# Retrotink5x_backwards.net
KiCad netlist of a schematic drawn in EAGLE
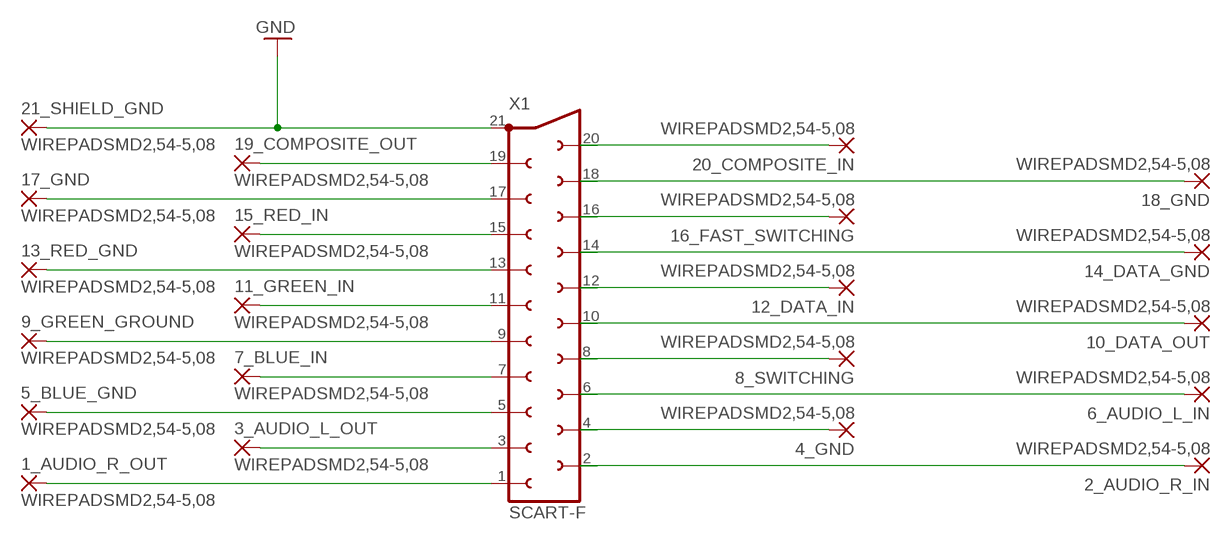
[diagram p0: schematic, sheet 1]

(export (version "E")
  (design (tool "Eeschema 10.0.6"))
  (components
    (comp (ref "1_AUDIO_R_OUT")
      (value "WIREPADSMD2,54-5,08")
      (footprint "eagle-import:SMD2,54-5,08")
      (libsource (lib "eagle-import") (part "WIREPADSMD2,54-5,08"))
    )
    (comp (ref "2_AUDIO_R_IN")
      (value "WIREPADSMD2,54-5,08")
      (footprint "eagle-import:SMD2,54-5,08")
      (libsource (lib "eagle-import") (part "WIREPADSMD2,54-5,08"))
    )
    (comp (ref "3_AUDIO_L_OUT")
      (value "WIREPADSMD2,54-5,08")
      (footprint "eagle-import:SMD2,54-5,08")
      (libsource (lib "eagle-import") (part "WIREPADSMD2,54-5,08"))
    )
    (comp (ref "4_GND")
      (value "WIREPADSMD2,54-5,08")
      (footprint "eagle-import:SMD2,54-5,08")
      (libsource (lib "eagle-import") (part "WIREPADSMD2,54-5,08"))
    )
    (comp (ref "5_BLUE_GND")
      (value "WIREPADSMD2,54-5,08")
      (footprint "eagle-import:SMD2,54-5,08")
      (libsource (lib "eagle-import") (part "WIREPADSMD2,54-5,08"))
    )
    (comp (ref "6_AUDIO_L_IN")
      (value "WIREPADSMD2,54-5,08")
      (footprint "eagle-import:SMD2,54-5,08")
      (libsource (lib "eagle-import") (part "WIREPADSMD2,54-5,08"))
    )
    (comp (ref "7_BLUE_IN")
      (value "WIREPADSMD2,54-5,08")
      (footprint "eagle-import:SMD2,54-5,08")
      (libsource (lib "eagle-import") (part "WIREPADSMD2,54-5,08"))
    )
    (comp (ref "8_SWITCHING")
      (value "WIREPADSMD2,54-5,08")
      (footprint "eagle-import:SMD2,54-5,08")
      (libsource (lib "eagle-import") (part "WIREPADSMD2,54-5,08"))
    )
    (comp (ref "9_GREEN_GROUND")
      (value "WIREPADSMD2,54-5,08")
      (footprint "eagle-import:SMD2,54-5,08")
      (libsource (lib "eagle-import") (part "WIREPADSMD2,54-5,08"))
    )
    (comp (ref "10_DATA_OUT")
      (value "WIREPADSMD2,54-5,08")
      (footprint "eagle-import:SMD2,54-5,08")
      (libsource (lib "eagle-import") (part "WIREPADSMD2,54-5,08"))
    )
    (comp (ref "11_GREEN_IN")
      (value "WIREPADSMD2,54-5,08")
      (footprint "eagle-import:SMD2,54-5,08")
      (libsource (lib "eagle-import") (part "WIREPADSMD2,54-5,08"))
    )
    (comp (ref "12_DATA_IN")
      (value "WIREPADSMD2,54-5,08")
      (footprint "eagle-import:SMD2,54-5,08")
      (libsource (lib "eagle-import") (part "WIREPADSMD2,54-5,08"))
    )
    (comp (ref "13_RED_GND")
      (value "WIREPADSMD2,54-5,08")
      (footprint "eagle-import:SMD2,54-5,08")
      (libsource (lib "eagle-import") (part "WIREPADSMD2,54-5,08"))
    )
    (comp (ref "14_DATA_GND")
      (value "WIREPADSMD2,54-5,08")
      (footprint "eagle-import:SMD2,54-5,08")
      (libsource (lib "eagle-import") (part "WIREPADSMD2,54-5,08"))
    )
    (comp (ref "15_RED_IN")
      (value "WIREPADSMD2,54-5,08")
      (footprint "eagle-import:SMD2,54-5,08")
      (libsource (lib "eagle-import") (part "WIREPADSMD2,54-5,08"))
    )
    (comp (ref "16_FAST_SWITCHING")
      (value "WIREPADSMD2,54-5,08")
      (footprint "eagle-import:SMD2,54-5,08")
      (libsource (lib "eagle-import") (part "WIREPADSMD2,54-5,08"))
    )
    (comp (ref "17_GND")
      (value "WIREPADSMD2,54-5,08")
      (footprint "eagle-import:SMD2,54-5,08")
      (libsource (lib "eagle-import") (part "WIREPADSMD2,54-5,08"))
    )
    (comp (ref "18_GND")
      (value "WIREPADSMD2,54-5,08")
      (footprint "eagle-import:SMD2,54-5,08")
      (libsource (lib "eagle-import") (part "WIREPADSMD2,54-5,08"))
    )
    (comp (ref "19_COMPOSITE_OUT")
      (value "WIREPADSMD2,54-5,08")
      (footprint "eagle-import:SMD2,54-5,08")
      (libsource (lib "eagle-import") (part "WIREPADSMD2,54-5,08"))
    )
    (comp (ref "20_COMPOSITE_IN")
      (value "WIREPADSMD2,54-5,08")
      (footprint "eagle-import:SMD2,54-5,08")
      (libsource (lib "eagle-import") (part "WIREPADSMD2,54-5,08"))
    )
    (comp (ref "21_SHIELD_GND")
      (value "WIREPADSMD2,54-5,08")
      (footprint "eagle-import:SMD2,54-5,08")
      (libsource (lib "eagle-import") (part "WIREPADSMD2,54-5,08"))
    )
    (comp (ref "X1")
      (value "SCART-F")
      (footprint "eagle-import:SCART-F")
      (libsource (lib "eagle-import") (part "SCART-F"))
    )
  )
  (nets
    (net (code "1") (name "GND") (class "Default")
      (node (ref "21_SHIELD_GND") (pin "1") (pinfunction "P_1") (pintype "passive"))
      (node (ref "X1") (pin "21") (pinfunction "21_21") (pintype "passive"))
    )
    (net (code "2") (name "Net-(1_AUDIO_R_OUT-P)") (class "Default")
      (node (ref "1_AUDIO_R_OUT") (pin "1") (pinfunction "P_1") (pintype "passive"))
      (node (ref "X1") (pin "1") (pinfunction "1_1") (pintype "passive"))
    )
    (net (code "3") (name "Net-(2_AUDIO_R_IN-P)") (class "Default")
      (node (ref "2_AUDIO_R_IN") (pin "1") (pinfunction "P_1") (pintype "passive"))
      (node (ref "X1") (pin "2") (pinfunction "2_2") (pintype "passive"))
    )
    (net (code "4") (name "Net-(3_AUDIO_L_OUT-P)") (class "Default")
      (node (ref "3_AUDIO_L_OUT") (pin "1") (pinfunction "P_1") (pintype "passive"))
      (node (ref "X1") (pin "3") (pinfunction "3_3") (pintype "passive"))
    )
    (net (code "5") (name "Net-(4_GND-P)") (class "Default")
      (node (ref "4_GND") (pin "1") (pinfunction "P_1") (pintype "passive"))
      (node (ref "X1") (pin "4") (pinfunction "4_4") (pintype "passive"))
    )
    (net (code "6") (name "Net-(5_BLUE_GND-P)") (class "Default")
      (node (ref "5_BLUE_GND") (pin "1") (pinfunction "P_1") (pintype "passive"))
      (node (ref "X1") (pin "5") (pinfunction "5_5") (pintype "passive"))
    )
    (net (code "7") (name "Net-(6_AUDIO_L_IN-P)") (class "Default")
      (node (ref "6_AUDIO_L_IN") (pin "1") (pinfunction "P_1") (pintype "passive"))
      (node (ref "X1") (pin "6") (pinfunction "6_6") (pintype "passive"))
    )
    (net (code "8") (name "Net-(7_BLUE_IN-P)") (class "Default")
      (node (ref "7_BLUE_IN") (pin "1") (pinfunction "P_1") (pintype "passive"))
      (node (ref "X1") (pin "7") (pinfunction "7_7") (pintype "passive"))
    )
    (net (code "9") (name "Net-(8_SWITCHING-P)") (class "Default")
      (node (ref "8_SWITCHING") (pin "1") (pinfunction "P_1") (pintype "passive"))
      (node (ref "X1") (pin "8") (pinfunction "8_8") (pintype "passive"))
    )
    (net (code "10") (name "Net-(9_GREEN_GROUND-P)") (class "Default")
      (node (ref "9_GREEN_GROUND") (pin "1") (pinfunction "P_1") (pintype "passive"))
      (node (ref "X1") (pin "9") (pinfunction "9_9") (pintype "passive"))
    )
    (net (code "11") (name "Net-(10_DATA_OUT-P)") (class "Default")
      (node (ref "10_DATA_OUT") (pin "1") (pinfunction "P_1") (pintype "passive"))
      (node (ref "X1") (pin "10") (pinfunction "10_10") (pintype "passive"))
    )
    (net (code "12") (name "Net-(11_GREEN_IN-P)") (class "Default")
      (node (ref "11_GREEN_IN") (pin "1") (pinfunction "P_1") (pintype "passive"))
      (node (ref "X1") (pin "11") (pinfunction "11_11") (pintype "passive"))
    )
    (net (code "13") (name "Net-(12_DATA_IN-P)") (class "Default")
      (node (ref "12_DATA_IN") (pin "1") (pinfunction "P_1") (pintype "passive"))
      (node (ref "X1") (pin "12") (pinfunction "12_12") (pintype "passive"))
    )
    (net (code "14") (name "Net-(13_RED_GND-P)") (class "Default")
      (node (ref "13_RED_GND") (pin "1") (pinfunction "P_1") (pintype "passive"))
      (node (ref "X1") (pin "13") (pinfunction "13_13") (pintype "passive"))
    )
    (net (code "15") (name "Net-(14_DATA_GND-P)") (class "Default")
      (node (ref "14_DATA_GND") (pin "1") (pinfunction "P_1") (pintype "passive"))
      (node (ref "X1") (pin "14") (pinfunction "14_14") (pintype "passive"))
    )
    (net (code "16") (name "Net-(15_RED_IN-P)") (class "Default")
      (node (ref "15_RED_IN") (pin "1") (pinfunction "P_1") (pintype "passive"))
      (node (ref "X1") (pin "15") (pinfunction "15_15") (pintype "passive"))
    )
    (net (code "17") (name "Net-(16_FAST_SWITCHING-P)") (class "Default")
      (node (ref "16_FAST_SWITCHING") (pin "1") (pinfunction "P_1") (pintype "passive"))
      (node (ref "X1") (pin "16") (pinfunction "16_16") (pintype "passive"))
    )
    (net (code "18") (name "Net-(17_GND-P)") (class "Default")
      (node (ref "17_GND") (pin "1") (pinfunction "P_1") (pintype "passive"))
      (node (ref "X1") (pin "17") (pinfunction "17_17") (pintype "passive"))
    )
    (net (code "19") (name "Net-(18_GND-P)") (class "Default")
      (node (ref "18_GND") (pin "1") (pinfunction "P_1") (pintype "passive"))
      (node (ref "X1") (pin "18") (pinfunction "18_18") (pintype "passive"))
    )
    (net (code "20") (name "Net-(19_COMPOSITE_OUT-P)") (class "Default")
      (node (ref "19_COMPOSITE_OUT") (pin "1") (pinfunction "P_1") (pintype "passive"))
      (node (ref "X1") (pin "19") (pinfunction "19_19") (pintype "passive"))
    )
    (net (code "21") (name "Net-(20_COMPOSITE_IN-P)") (class "Default")
      (node (ref "20_COMPOSITE_IN") (pin "1") (pinfunction "P_1") (pintype "passive"))
      (node (ref "X1") (pin "20") (pinfunction "20_20") (pintype "passive"))
    )
  )
)
